# klokun.net
KiCad netlist of a schematic drawn in Altium Designer
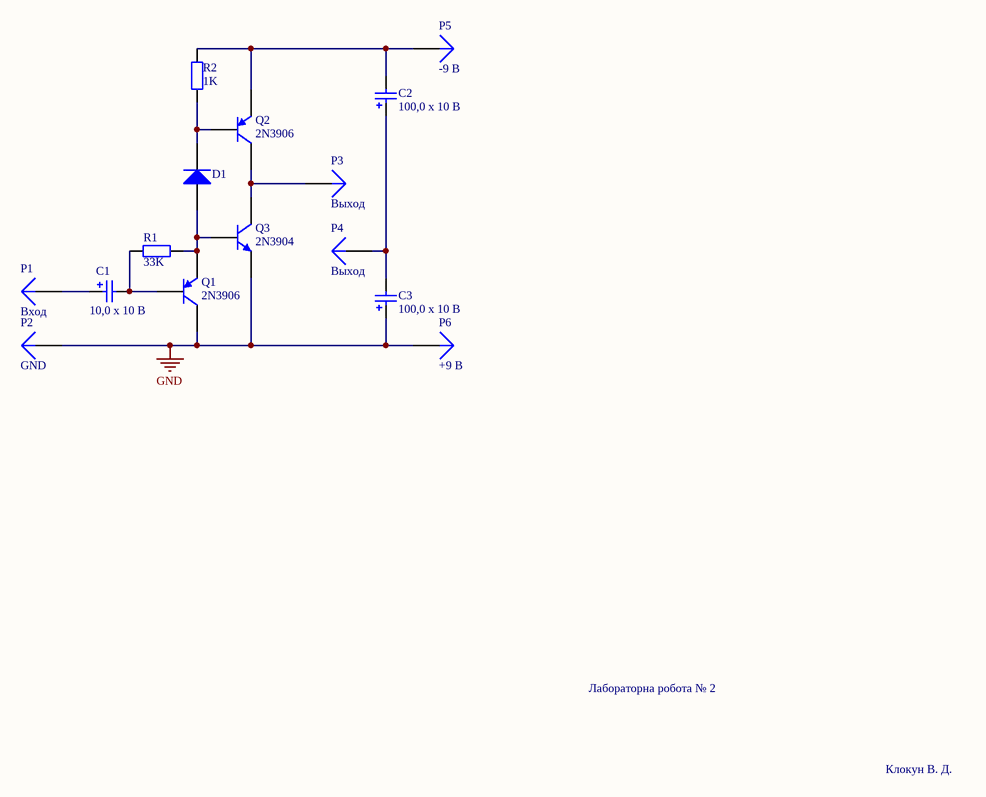
[diagram p0: klokun.SchDoc]

(export (version "E")
  (design (tool "Eeschema 10.0.6"))
  (components
    (comp (ref "C1")
      (value "10,0 x 10 В")
      (footprint "POLAR0.8")
      (description "Polarized Capacitor (Axial)")
      (fields (field (name "Comment") "Cap Pol2") (field (name "PUBLISHER") "Altium Limited"))
      (libsource (lib "Miscellaneous Devices") (part "Cap Pol2"))
    )
    (comp (ref "C2")
      (value "100,0 x 10 В")
      (footprint "POLAR0.8")
      (description "Polarized Capacitor (Axial)")
      (fields (field (name "Comment") "Cap Pol2") (field (name "PUBLISHER") "Altium Limited"))
      (libsource (lib "Miscellaneous Devices") (part "Cap Pol2"))
    )
    (comp (ref "C3")
      (value "100,0 x 10 В")
      (footprint "POLAR0.8")
      (description "Polarized Capacitor (Axial)")
      (fields (field (name "Comment") "Cap Pol2") (field (name "PUBLISHER") "Altium Limited"))
      (libsource (lib "Miscellaneous Devices") (part "Cap Pol2"))
    )
    (comp (ref "D1")
      (value "Diode 1N4148")
      (footprint "DO-35")
      (description "High Conductance Fast Diode")
      (fields (field (name "PUBLISHER") "Altium Limited"))
      (libsource (lib "Miscellaneous Devices") (part "Diode 1N4148"))
    )
    (comp (ref "P1")
      (value "Вход")
      (footprint "PIN1")
      (description "Plug")
      (fields (field (name "PUBLISHER") "Altium Limited"))
      (libsource (lib "Miscellaneous Connectors") (part "Plug"))
    )
    (comp (ref "P2")
      (value "GND")
      (footprint "PIN1")
      (description "Plug")
      (fields (field (name "PUBLISHER") "Altium Limited"))
      (libsource (lib "Miscellaneous Connectors") (part "Plug"))
    )
    (comp (ref "P3")
      (value "Выход")
      (footprint "PIN1")
      (description "Plug")
      (fields (field (name "PUBLISHER") "Altium Limited"))
      (libsource (lib "Miscellaneous Connectors") (part "Plug"))
    )
    (comp (ref "P4")
      (value "Выход")
      (footprint "PIN1")
      (description "Plug")
      (fields (field (name "PUBLISHER") "Altium Limited"))
      (libsource (lib "Miscellaneous Connectors") (part "Plug"))
    )
    (comp (ref "P5")
      (value "-9 В")
      (footprint "PIN1")
      (description "Plug")
      (fields (field (name "PUBLISHER") "Altium Limited"))
      (libsource (lib "Miscellaneous Connectors") (part "Plug"))
    )
    (comp (ref "P6")
      (value "+9 В")
      (footprint "PIN1")
      (description "Plug")
      (fields (field (name "PUBLISHER") "Altium Limited"))
      (libsource (lib "Miscellaneous Connectors") (part "Plug"))
    )
    (comp (ref "Q1")
      (value "2N3906")
      (footprint "TO-92A")
      (description "PNP General Purpose Amplifier")
      (fields (field (name "PUBLISHER") "Altium Limited"))
      (libsource (lib "Miscellaneous Devices") (part "2N3906"))
    )
    (comp (ref "Q2")
      (value "2N3906")
      (footprint "TO-92A")
      (description "PNP General Purpose Amplifier")
      (fields (field (name "PUBLISHER") "Altium Limited"))
      (libsource (lib "Miscellaneous Devices") (part "2N3906"))
    )
    (comp (ref "Q3")
      (value "2N3904")
      (footprint "TO-92A")
      (description "NPN General Purpose Amplifier")
      (fields (field (name "PUBLISHER") "Altium Limited"))
      (libsource (lib "Miscellaneous Devices") (part "2N3904"))
    )
    (comp (ref "R1")
      (value "33K")
      (footprint "AXIAL-0.4")
      (description "Resistor")
      (fields (field (name "Comment") "Res2") (field (name "PUBLISHER") "Altium Limited"))
      (libsource (lib "Miscellaneous Devices") (part "Res2"))
    )
    (comp (ref "R2")
      (value "1K")
      (footprint "AXIAL-0.4")
      (description "Resistor")
      (fields (field (name "Comment") "Res2") (field (name "PUBLISHER") "Altium Limited"))
      (libsource (lib "") (part "Res2_1"))
    )
  )
  (nets
    (net (code "1") (name "GND") (class "Default")
      (node (ref "C3") (pin "1") (pinfunction "1_1") (pintype "passive"))
      (node (ref "P2") (pin "1") (pinfunction "1_1") (pintype "passive"))
      (node (ref "P6") (pin "1") (pinfunction "1_1") (pintype "passive"))
      (node (ref "Q1") (pin "3") (pinfunction "C_3") (pintype "passive"))
      (node (ref "Q3") (pin "1") (pinfunction "E_1") (pintype "passive"))
    )
    (net (code "2") (name "Net-(C1-Pad1)") (class "Default")
      (node (ref "C1") (pin "1") (pinfunction "1_1") (pintype "passive"))
      (node (ref "P1") (pin "1") (pinfunction "1_1") (pintype "passive"))
    )
    (net (code "3") (name "Net-(C2-Pad1)") (class "Default")
      (node (ref "C2") (pin "1") (pinfunction "1_1") (pintype "passive"))
      (node (ref "C3") (pin "2") (pinfunction "2_2") (pintype "passive"))
      (node (ref "P4") (pin "1") (pinfunction "1_1") (pintype "passive"))
    )
    (net (code "4") (name "Net-(D1-A)") (class "Default")
      (node (ref "D1") (pin "1") (pinfunction "A_1") (pintype "passive"))
      (node (ref "Q1") (pin "1") (pinfunction "E_1") (pintype "passive"))
      (node (ref "Q3") (pin "2") (pinfunction "B_2") (pintype "passive"))
      (node (ref "R1") (pin "2") (pinfunction "2_2") (pintype "passive"))
    )
    (net (code "5") (name "Net-(D1-K)") (class "Default")
      (node (ref "D1") (pin "2") (pinfunction "K_2") (pintype "passive"))
      (node (ref "Q2") (pin "2") (pinfunction "B_2") (pintype "passive"))
      (node (ref "R2") (pin "1") (pinfunction "1_1") (pintype "passive"))
    )
    (net (code "6") (name "Net-(Q1-B)") (class "Default")
      (node (ref "C1") (pin "2") (pinfunction "2_2") (pintype "passive"))
      (node (ref "Q1") (pin "2") (pinfunction "B_2") (pintype "passive"))
      (node (ref "R1") (pin "1") (pinfunction "1_1") (pintype "passive"))
    )
    (net (code "7") (name "Net-(Q2-C)") (class "Default")
      (node (ref "P3") (pin "1") (pinfunction "1_1") (pintype "passive"))
      (node (ref "Q2") (pin "3") (pinfunction "C_3") (pintype "passive"))
      (node (ref "Q3") (pin "3") (pinfunction "C_3") (pintype "passive"))
    )
    (net (code "8") (name "Net-(Q2-E)") (class "Default")
      (node (ref "C2") (pin "2") (pinfunction "2_2") (pintype "passive"))
      (node (ref "P5") (pin "1") (pinfunction "1_1") (pintype "passive"))
      (node (ref "Q2") (pin "1") (pinfunction "E_1") (pintype "passive"))
      (node (ref "R2") (pin "2") (pinfunction "2_2") (pintype "passive"))
    )
  )
)
